# Amplifier.net
KiCad netlist of a schematic drawn in EAGLE
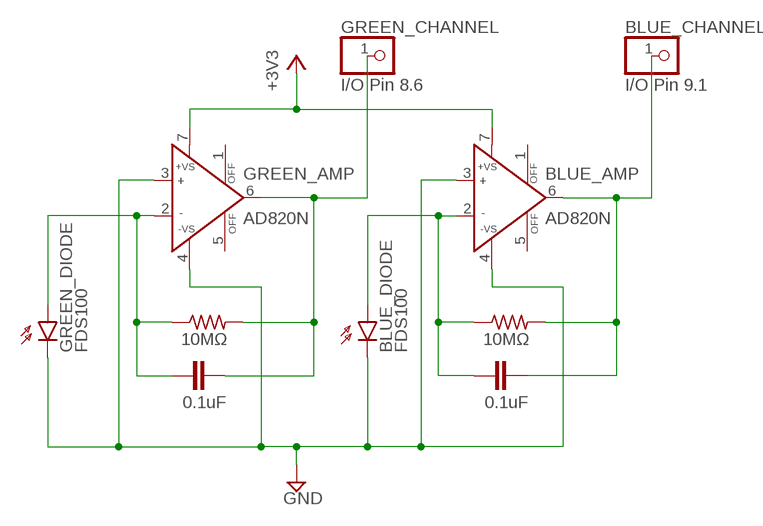
[diagram p0: schematic, sheet 1]

(export (version "E")
  (design (tool "Eeschema 10.0.6"))
  (components
    (comp (ref "BLUE_AMP")
      (value "AD820N")
      (footprint "eagle-import:DIL08")
      (libsource (lib "eagle-import") (part "AD820N"))
    )
    (comp (ref "BLUE_CHANNEL")
      (value "I/O Pin 9.1")
      (footprint "eagle-import:1X01")
      (libsource (lib "eagle-import") (part "PINHD-1X1"))
    )
    (comp (ref "BLUE_DIODE")
      (value "FDS100")
      (footprint "eagle-import:BPX65")
      (fields (field (name "MPN") "BPX65."))
      (libsource (lib "eagle-import") (part "BPX65"))
    )
    (comp (ref "C1")
      (value "0.1uF")
      (footprint "eagle-import:C2.5-3")
      (libsource (lib "eagle-import") (part "C2,5-3"))
    )
    (comp (ref "C2")
      (value "0.1uF")
      (footprint "eagle-import:C2.5-3")
      (libsource (lib "eagle-import") (part "C2,5-3"))
    )
    (comp (ref "GREEN_AMP")
      (value "AD820N")
      (footprint "eagle-import:DIL08")
      (libsource (lib "eagle-import") (part "AD820N"))
    )
    (comp (ref "GREEN_CHANNEL")
      (value "I/O Pin 8.6")
      (footprint "eagle-import:1X01")
      (libsource (lib "eagle-import") (part "PINHD-1X1"))
    )
    (comp (ref "GREEN_DIODE")
      (value "FDS100")
      (footprint "eagle-import:BPX65")
      (fields (field (name "MPN") "BPX65."))
      (libsource (lib "eagle-import") (part "BPX65"))
    )
    (comp (ref "R1")
      (value "10MΩ")
      (footprint "eagle-import:0207_12")
      (libsource (lib "eagle-import") (part "R-US_0207/12"))
    )
    (comp (ref "R2")
      (value "10MΩ")
      (footprint "eagle-import:0207_12")
      (libsource (lib "eagle-import") (part "R-US_0207/12"))
    )
  )
  (nets
    (net (code "1") (name "+3V3") (class "Default")
      (node (ref "BLUE_AMP") (pin "7") (pinfunction "+VS_7") (pintype "input"))
      (node (ref "GREEN_AMP") (pin "7") (pinfunction "+VS_7") (pintype "input"))
    )
    (net (code "2") (name "GND") (class "Default")
      (node (ref "BLUE_AMP") (pin "3") (pinfunction "IN+_3") (pintype "input"))
      (node (ref "BLUE_AMP") (pin "4") (pinfunction "-VS_4") (pintype "input"))
      (node (ref "BLUE_DIODE") (pin "K") (pinfunction "C_K") (pintype "passive"))
      (node (ref "GREEN_AMP") (pin "3") (pinfunction "IN+_3") (pintype "input"))
      (node (ref "GREEN_AMP") (pin "4") (pinfunction "-VS_4") (pintype "input"))
      (node (ref "GREEN_DIODE") (pin "K") (pinfunction "C_K") (pintype "passive"))
    )
    (net (code "3") (name "Net-(BLUE_AMP-IN-)") (class "Default")
      (node (ref "BLUE_AMP") (pin "2") (pinfunction "IN-_2") (pintype "input"))
      (node (ref "BLUE_DIODE") (pin "A") (pinfunction "A_A") (pintype "passive"))
      (node (ref "C2") (pin "2") (pinfunction "2_2") (pintype "passive"))
      (node (ref "R2") (pin "1") (pinfunction "1_1") (pintype "passive"))
    )
    (net (code "4") (name "Net-(BLUE_AMP-OUT)") (class "Default")
      (node (ref "BLUE_AMP") (pin "6") (pinfunction "OUT_6") (pintype "output"))
      (node (ref "BLUE_CHANNEL") (pin "1") (pinfunction "1_1") (pintype "passive"))
      (node (ref "C2") (pin "1") (pinfunction "1_1") (pintype "passive"))
      (node (ref "R2") (pin "2") (pinfunction "2_2") (pintype "passive"))
    )
    (net (code "5") (name "Net-(GREEN_AMP-IN-)") (class "Default")
      (node (ref "C1") (pin "2") (pinfunction "2_2") (pintype "passive"))
      (node (ref "GREEN_AMP") (pin "2") (pinfunction "IN-_2") (pintype "input"))
      (node (ref "GREEN_DIODE") (pin "A") (pinfunction "A_A") (pintype "passive"))
      (node (ref "R1") (pin "1") (pinfunction "1_1") (pintype "passive"))
    )
    (net (code "6") (name "Net-(GREEN_AMP-OUT)") (class "Default")
      (node (ref "C1") (pin "1") (pinfunction "1_1") (pintype "passive"))
      (node (ref "GREEN_AMP") (pin "6") (pinfunction "OUT_6") (pintype "output"))
      (node (ref "GREEN_CHANNEL") (pin "1") (pinfunction "1_1") (pintype "passive"))
      (node (ref "R1") (pin "2") (pinfunction "2_2") (pintype "passive"))
    )
    (net (code "7") (name "unconnected-(BLUE_AMP-OFF-Pad1)") (class "Default")
      (node (ref "BLUE_AMP") (pin "1") (pinfunction "OFF_1") (pintype "passive"))
    )
    (net (code "8") (name "unconnected-(BLUE_AMP-OFF-Pad5)") (class "Default")
      (node (ref "BLUE_AMP") (pin "5") (pinfunction "OFF_5") (pintype "passive"))
    )
    (net (code "9") (name "unconnected-(GREEN_AMP-OFF-Pad1)") (class "Default")
      (node (ref "GREEN_AMP") (pin "1") (pinfunction "OFF_1") (pintype "passive"))
    )
    (net (code "10") (name "unconnected-(GREEN_AMP-OFF-Pad5)") (class "Default")
      (node (ref "GREEN_AMP") (pin "5") (pinfunction "OFF_5") (pintype "passive"))
    )
  )
)
